# DM3390_Connector_C.net
KiCad netlist of a schematic drawn in Altium Designer
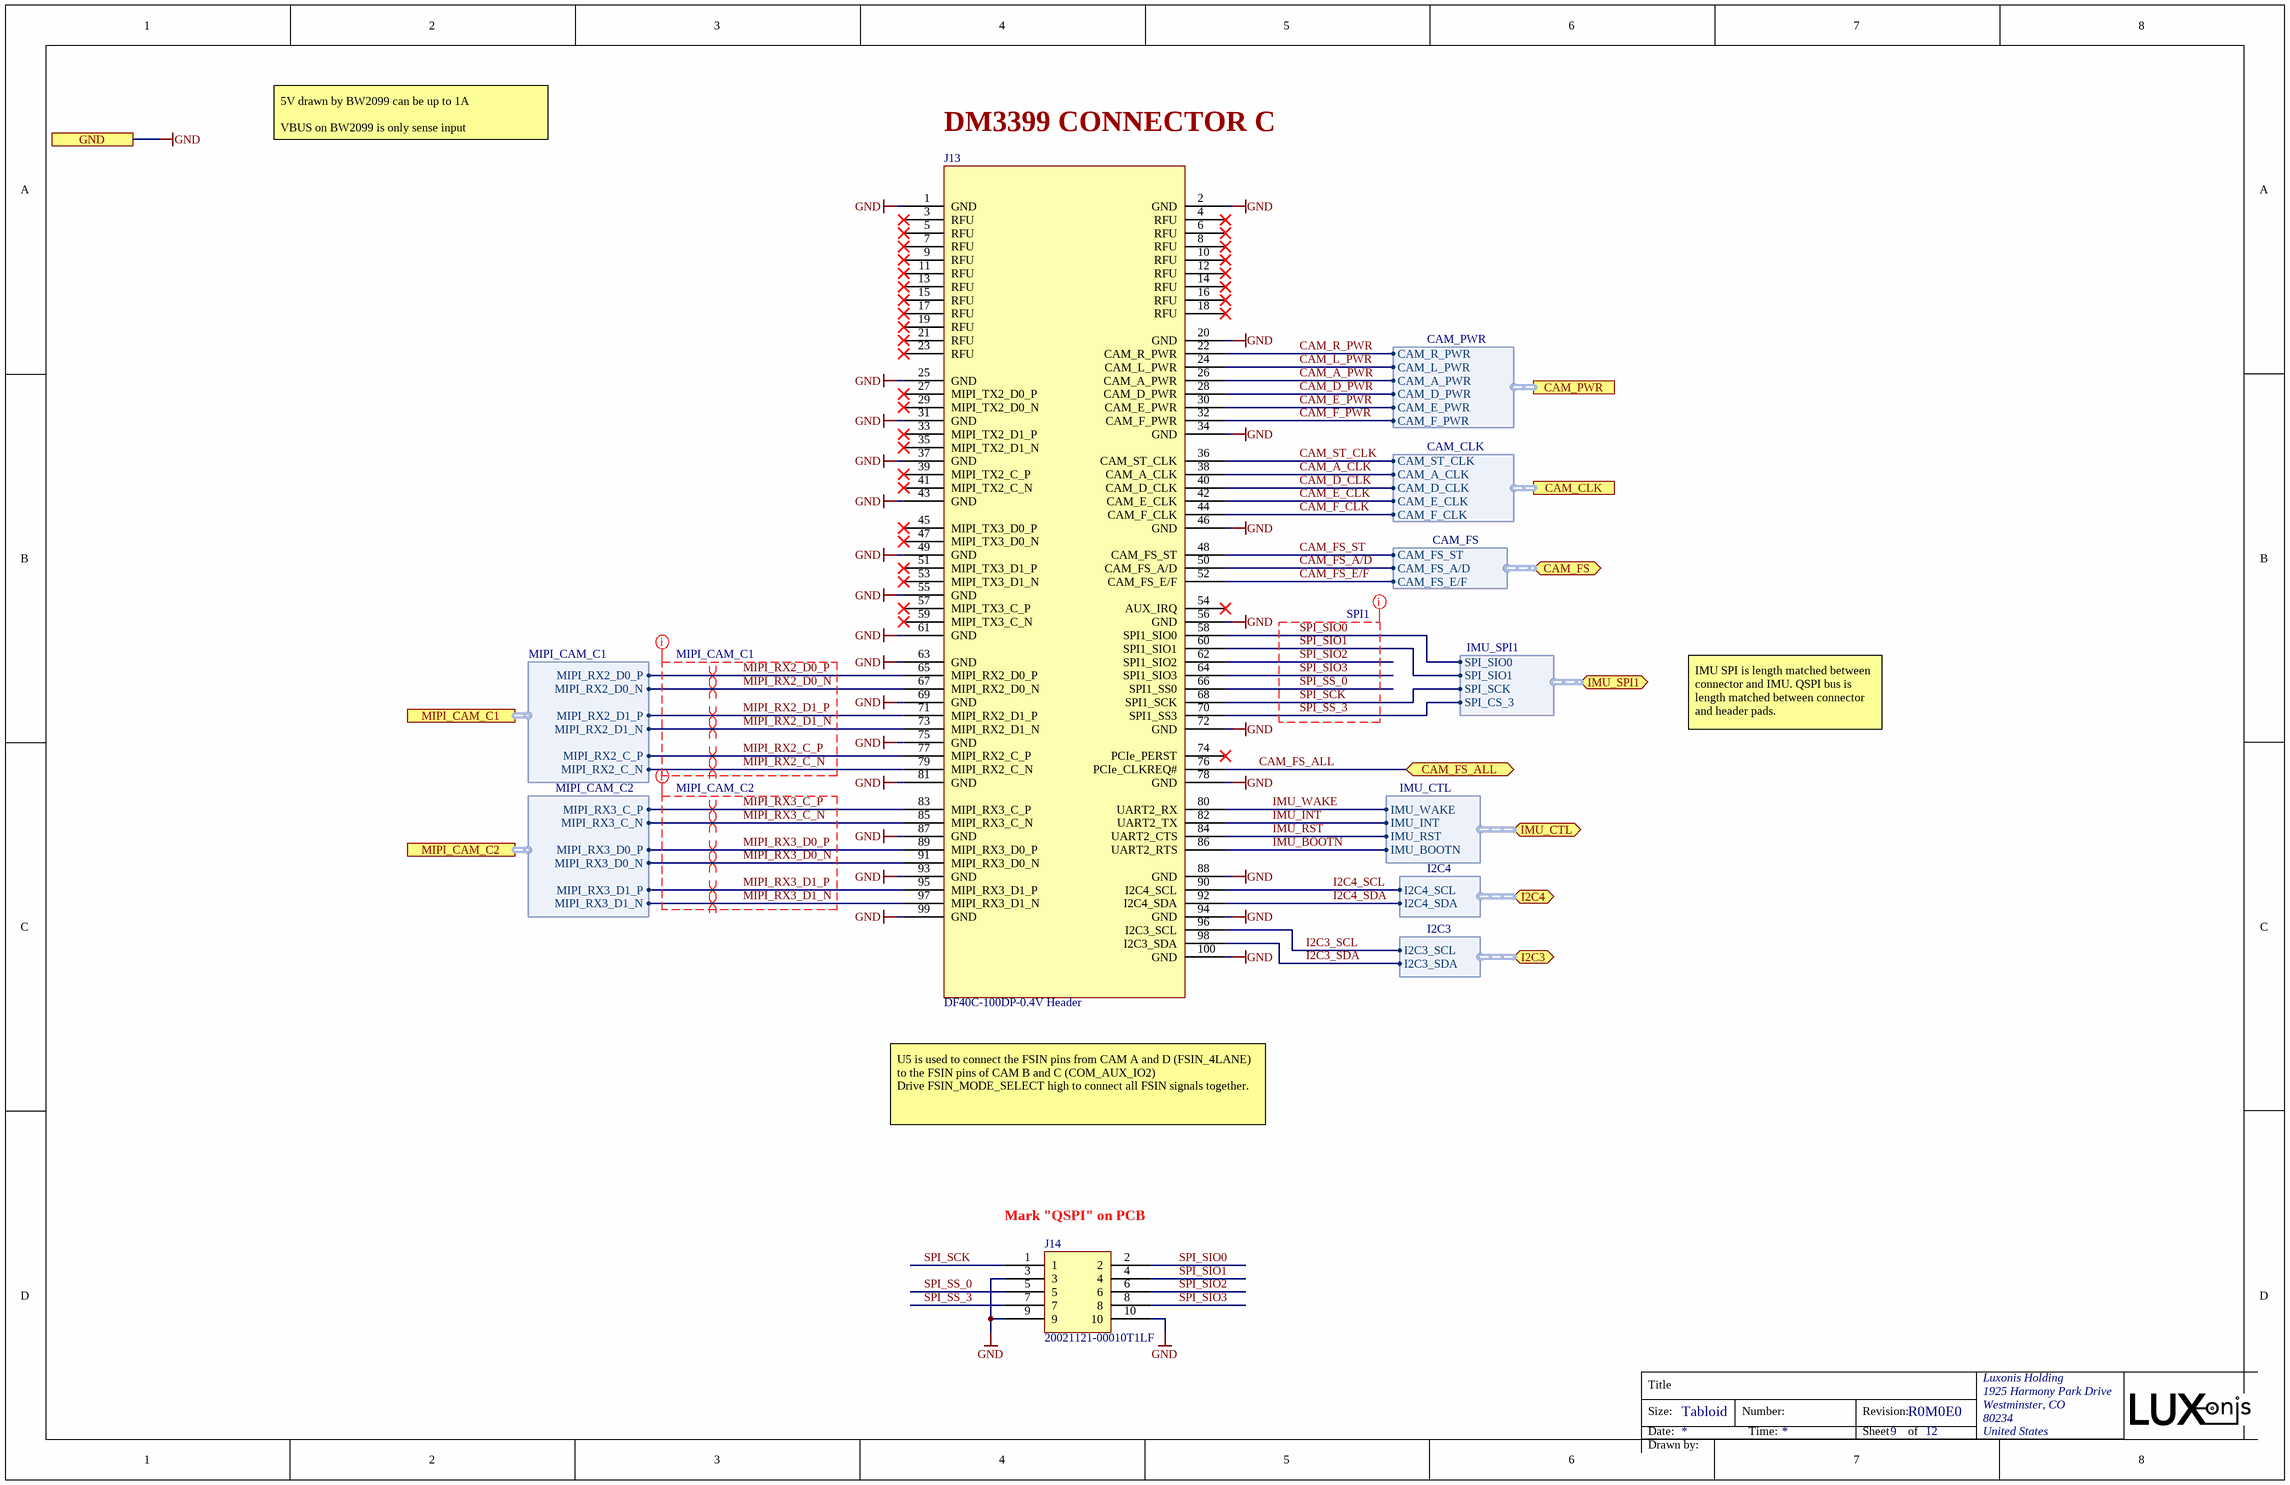
[diagram p0: DM3390_Connector_C.SchDoc]

(export (version "E")
  (design (tool "Eeschema 10.0.6"))
  (components
    (comp (ref "J13")
      (value "DF40C-100DP-0.4V Header")
      (footprint "LuxonisMaster:CON_C_SoM-MAX_DF40HC-3.0-100DS-0.4V_minpad")
      (description "CONN HDR 100POS 0.4MM SMD GOLD BW2099 SYMBOL")
      (fields (field (name "MFG") "Hirose"))
      (libsource (lib "LuxonisMaster") (part "DF40HC(3.0)-100DS-0.4V_OAK-SoM-MAX_C"))
    )
    (comp (ref "J14")
      (value "20021121-00010T1LF")
      (footprint "LuxonisMaster:20021121-00010T1LF")
      (description "CONN HEADER SMD 10POS 1.27MM")
      (libsource (lib "LuxonisMaster") (part "20021121-00010T1LF"))
    )
  )
  (nets
    (net (code "10") (name "/CAM_A_CLK") (class "Default")
      (node (ref "J13") (pin "38") (pinfunction "CAM_A_CLK_38") (pintype "passive"))
    )
    (net (code "11") (name "/CAM_A_PWR") (class "Default")
      (node (ref "J13") (pin "26") (pinfunction "CAM_A_PWR_26") (pintype "passive"))
    )
    (net (code "12") (name "/CAM_D_CLK") (class "Default")
      (node (ref "J13") (pin "40") (pinfunction "CAM_D_CLK_40") (pintype "passive"))
    )
    (net (code "13") (name "/CAM_D_PWR") (class "Default")
      (node (ref "J13") (pin "28") (pinfunction "CAM_D_PWR_28") (pintype "passive"))
    )
    (net (code "14") (name "/CAM_E_CLK") (class "Default")
      (node (ref "J13") (pin "42") (pinfunction "CAM_E_CLK_42") (pintype "passive"))
    )
    (net (code "15") (name "/CAM_E_PWR") (class "Default")
      (node (ref "J13") (pin "30") (pinfunction "CAM_E_PWR_30") (pintype "passive"))
    )
    (net (code "16") (name "/CAM_FS_ALL") (class "Default")
      (node (ref "J13") (pin "76") (pinfunction "PCIe_CLKREQ#_76") (pintype "passive"))
    )
    (net (code "17") (name "/CAM_FS_A{slash}D") (class "Default")
      (node (ref "J13") (pin "50") (pinfunction "CAM_FS_A/D_50") (pintype "passive"))
    )
    (net (code "18") (name "/CAM_FS_E{slash}F") (class "Default")
      (node (ref "J13") (pin "52") (pinfunction "CAM_FS_E/F_52") (pintype "passive"))
    )
    (net (code "19") (name "/CAM_FS_ST") (class "Default")
      (node (ref "J13") (pin "48") (pinfunction "CAM_FS_ST_48") (pintype "passive"))
    )
    (net (code "20") (name "/CAM_F_CLK") (class "Default")
      (node (ref "J13") (pin "44") (pinfunction "CAM_F_CLK_44") (pintype "passive"))
    )
    (net (code "21") (name "/CAM_F_PWR") (class "Default")
      (node (ref "J13") (pin "32") (pinfunction "CAM_F_PWR_32") (pintype "passive"))
    )
    (net (code "22") (name "/CAM_L_PWR") (class "Default")
      (node (ref "J13") (pin "24") (pinfunction "CAM_L_PWR_24") (pintype "passive"))
    )
    (net (code "23") (name "/CAM_R_PWR") (class "Default")
      (node (ref "J13") (pin "22") (pinfunction "CAM_R_PWR_22") (pintype "passive"))
    )
    (net (code "24") (name "/CAM_ST_CLK") (class "Default")
      (node (ref "J13") (pin "36") (pinfunction "CAM_ST_CLK_36") (pintype "passive"))
    )
    (net (code "25") (name "/I2C3_SCL") (class "Default")
      (node (ref "J13") (pin "96") (pinfunction "I2C3_SCL_96") (pintype "passive"))
    )
    (net (code "26") (name "/I2C3_SDA") (class "Default")
      (node (ref "J13") (pin "98") (pinfunction "I2C3_SDA_98") (pintype "passive"))
    )
    (net (code "27") (name "/I2C4_SCL") (class "Default")
      (node (ref "J13") (pin "90") (pinfunction "I2C4_SCL_90") (pintype "passive"))
    )
    (net (code "28") (name "/I2C4_SDA") (class "Default")
      (node (ref "J13") (pin "92") (pinfunction "I2C4_SDA_92") (pintype "passive"))
    )
    (net (code "29") (name "/IMU_BOOTN") (class "Default")
      (node (ref "J13") (pin "86") (pinfunction "UART2_RTS_86") (pintype "passive"))
    )
    (net (code "30") (name "/IMU_INT") (class "Default")
      (node (ref "J13") (pin "82") (pinfunction "UART2_TX_82") (pintype "passive"))
    )
    (net (code "31") (name "/IMU_RST") (class "Default")
      (node (ref "J13") (pin "84") (pinfunction "UART2_CTS_84") (pintype "passive"))
    )
    (net (code "32") (name "/IMU_WAKE") (class "Default")
      (node (ref "J13") (pin "80") (pinfunction "UART2_RX_80") (pintype "passive"))
    )
    (net (code "33") (name "/MIPI_RX2_C_N") (class "Default")
      (node (ref "J13") (pin "79") (pinfunction "MIPI_RX2_C_N_79") (pintype "passive"))
    )
    (net (code "34") (name "/MIPI_RX2_C_P") (class "Default")
      (node (ref "J13") (pin "77") (pinfunction "MIPI_RX2_C_P_77") (pintype "passive"))
    )
    (net (code "35") (name "/MIPI_RX2_D0_N") (class "Default")
      (node (ref "J13") (pin "67") (pinfunction "MIPI_RX2_D0_N_67") (pintype "passive"))
    )
    (net (code "36") (name "/MIPI_RX2_D0_P") (class "Default")
      (node (ref "J13") (pin "65") (pinfunction "MIPI_RX2_D0_P_65") (pintype "passive"))
    )
    (net (code "37") (name "/MIPI_RX2_D1_N") (class "Default")
      (node (ref "J13") (pin "73") (pinfunction "MIPI_RX2_D1_N_73") (pintype "passive"))
    )
    (net (code "38") (name "/MIPI_RX2_D1_P") (class "Default")
      (node (ref "J13") (pin "71") (pinfunction "MIPI_RX2_D1_P_71") (pintype "passive"))
    )
    (net (code "39") (name "/MIPI_RX3_C_N") (class "Default")
      (node (ref "J13") (pin "85") (pinfunction "MIPI_RX3_C_N_85") (pintype "passive"))
    )
    (net (code "40") (name "/MIPI_RX3_C_P") (class "Default")
      (node (ref "J13") (pin "83") (pinfunction "MIPI_RX3_C_P_83") (pintype "passive"))
    )
    (net (code "41") (name "/MIPI_RX3_D0_N") (class "Default")
      (node (ref "J13") (pin "91") (pinfunction "MIPI_RX3_D0_N_91") (pintype "passive"))
    )
    (net (code "42") (name "/MIPI_RX3_D0_P") (class "Default")
      (node (ref "J13") (pin "89") (pinfunction "MIPI_RX3_D0_P_89") (pintype "passive"))
    )
    (net (code "43") (name "/MIPI_RX3_D1_N") (class "Default")
      (node (ref "J13") (pin "97") (pinfunction "MIPI_RX3_D1_N_97") (pintype "passive"))
    )
    (net (code "44") (name "/MIPI_RX3_D1_P") (class "Default")
      (node (ref "J13") (pin "95") (pinfunction "MIPI_RX3_D1_P_95") (pintype "passive"))
    )
    (net (code "45") (name "/SPI_SCK") (class "Default")
      (node (ref "J13") (pin "68") (pinfunction "SPI1_SCK_68") (pintype "passive"))
      (node (ref "J14") (pin "1") (pinfunction "1_1") (pintype "passive"))
    )
    (net (code "46") (name "/SPI_SIO0") (class "Default")
      (node (ref "J13") (pin "58") (pinfunction "SPI1_SIO0_58") (pintype "passive"))
      (node (ref "J14") (pin "2") (pinfunction "2_2") (pintype "passive"))
    )
    (net (code "47") (name "/SPI_SIO1") (class "Default")
      (node (ref "J13") (pin "60") (pinfunction "SPI1_SIO1_60") (pintype "passive"))
      (node (ref "J14") (pin "4") (pinfunction "4_4") (pintype "passive"))
    )
    (net (code "48") (name "/SPI_SIO2") (class "Default")
      (node (ref "J13") (pin "62") (pinfunction "SPI1_SIO2_62") (pintype "passive"))
      (node (ref "J14") (pin "6") (pinfunction "6_6") (pintype "passive"))
    )
    (net (code "49") (name "/SPI_SIO3") (class "Default")
      (node (ref "J13") (pin "64") (pinfunction "SPI1_SIO3_64") (pintype "passive"))
      (node (ref "J14") (pin "8") (pinfunction "8_8") (pintype "passive"))
    )
    (net (code "50") (name "/SPI_SS_0") (class "Default")
      (node (ref "J13") (pin "66") (pinfunction "SPI1_SS0_66") (pintype "passive"))
      (node (ref "J14") (pin "5") (pinfunction "5_5") (pintype "passive"))
    )
    (net (code "51") (name "/SPI_SS_3") (class "Default")
      (node (ref "J13") (pin "70") (pinfunction "SPI1_SS3_70") (pintype "passive"))
      (node (ref "J14") (pin "7") (pinfunction "7_7") (pintype "passive"))
    )
    (net (code "61") (name "GND") (class "Default")
      (node (ref "J13") (pin "1") (pinfunction "GND_1") (pintype "passive"))
      (node (ref "J13") (pin "100") (pinfunction "GND_100") (pintype "passive"))
      (node (ref "J13") (pin "2") (pinfunction "GND_2") (pintype "passive"))
      (node (ref "J13") (pin "20") (pinfunction "GND_20") (pintype "passive"))
      (node (ref "J13") (pin "25") (pinfunction "GND_25") (pintype "passive"))
      (node (ref "J13") (pin "31") (pinfunction "GND_31") (pintype "passive"))
      (node (ref "J13") (pin "34") (pinfunction "GND_34") (pintype "passive"))
      (node (ref "J13") (pin "37") (pinfunction "GND_37") (pintype "passive"))
      (node (ref "J13") (pin "43") (pinfunction "GND_43") (pintype "passive"))
      (node (ref "J13") (pin "46") (pinfunction "GND_46") (pintype "passive"))
      (node (ref "J13") (pin "49") (pinfunction "GND_49") (pintype "passive"))
      (node (ref "J13") (pin "55") (pinfunction "GND_55") (pintype "passive"))
      (node (ref "J13") (pin "56") (pinfunction "GND_56") (pintype "passive"))
      (node (ref "J13") (pin "61") (pinfunction "GND_61") (pintype "passive"))
      (node (ref "J13") (pin "63") (pinfunction "GND_63") (pintype "passive"))
      (node (ref "J13") (pin "69") (pinfunction "GND_69") (pintype "passive"))
      (node (ref "J13") (pin "72") (pinfunction "GND_72") (pintype "passive"))
      (node (ref "J13") (pin "75") (pinfunction "GND_75") (pintype "passive"))
      (node (ref "J13") (pin "78") (pinfunction "GND_78") (pintype "passive"))
      (node (ref "J13") (pin "81") (pinfunction "GND_81") (pintype "passive"))
      (node (ref "J13") (pin "87") (pinfunction "GND_87") (pintype "passive"))
      (node (ref "J13") (pin "88") (pinfunction "GND_88") (pintype "passive"))
      (node (ref "J13") (pin "93") (pinfunction "GND_93") (pintype "passive"))
      (node (ref "J13") (pin "94") (pinfunction "GND_94") (pintype "passive"))
      (node (ref "J13") (pin "99") (pinfunction "GND_99") (pintype "passive"))
      (node (ref "J14") (pin "10") (pinfunction "10_10") (pintype "passive"))
      (node (ref "J14") (pin "3") (pinfunction "3_3") (pintype "passive"))
      (node (ref "J14") (pin "9") (pinfunction "9_9") (pintype "passive"))
    )
    (net (code "62") (name "unconnected-(J13-AUX_IRQ-Pad54)") (class "Default")
      (node (ref "J13") (pin "54") (pinfunction "AUX_IRQ_54") (pintype "passive+no_connect"))
    )
    (net (code "63") (name "unconnected-(J13-MIPI_TX2_C_N-Pad41)") (class "Default")
      (node (ref "J13") (pin "41") (pinfunction "MIPI_TX2_C_N_41") (pintype "passive+no_connect"))
    )
    (net (code "64") (name "unconnected-(J13-MIPI_TX2_C_P-Pad39)") (class "Default")
      (node (ref "J13") (pin "39") (pinfunction "MIPI_TX2_C_P_39") (pintype "passive+no_connect"))
    )
    (net (code "65") (name "unconnected-(J13-MIPI_TX2_D0_N-Pad29)") (class "Default")
      (node (ref "J13") (pin "29") (pinfunction "MIPI_TX2_D0_N_29") (pintype "passive+no_connect"))
    )
    (net (code "66") (name "unconnected-(J13-MIPI_TX2_D0_P-Pad27)") (class "Default")
      (node (ref "J13") (pin "27") (pinfunction "MIPI_TX2_D0_P_27") (pintype "passive+no_connect"))
    )
    (net (code "67") (name "unconnected-(J13-MIPI_TX2_D1_N-Pad35)") (class "Default")
      (node (ref "J13") (pin "35") (pinfunction "MIPI_TX2_D1_N_35") (pintype "passive+no_connect"))
    )
    (net (code "68") (name "unconnected-(J13-MIPI_TX2_D1_P-Pad33)") (class "Default")
      (node (ref "J13") (pin "33") (pinfunction "MIPI_TX2_D1_P_33") (pintype "passive+no_connect"))
    )
    (net (code "69") (name "unconnected-(J13-MIPI_TX3_C_N-Pad59)") (class "Default")
      (node (ref "J13") (pin "59") (pinfunction "MIPI_TX3_C_N_59") (pintype "passive+no_connect"))
    )
    (net (code "70") (name "unconnected-(J13-MIPI_TX3_C_P-Pad57)") (class "Default")
      (node (ref "J13") (pin "57") (pinfunction "MIPI_TX3_C_P_57") (pintype "passive+no_connect"))
    )
    (net (code "71") (name "unconnected-(J13-MIPI_TX3_D0_N-Pad47)") (class "Default")
      (node (ref "J13") (pin "47") (pinfunction "MIPI_TX3_D0_N_47") (pintype "passive+no_connect"))
    )
    (net (code "72") (name "unconnected-(J13-MIPI_TX3_D0_P-Pad45)") (class "Default")
      (node (ref "J13") (pin "45") (pinfunction "MIPI_TX3_D0_P_45") (pintype "passive+no_connect"))
    )
    (net (code "73") (name "unconnected-(J13-MIPI_TX3_D1_N-Pad53)") (class "Default")
      (node (ref "J13") (pin "53") (pinfunction "MIPI_TX3_D1_N_53") (pintype "passive+no_connect"))
    )
    (net (code "74") (name "unconnected-(J13-MIPI_TX3_D1_P-Pad51)") (class "Default")
      (node (ref "J13") (pin "51") (pinfunction "MIPI_TX3_D1_P_51") (pintype "passive+no_connect"))
    )
    (net (code "75") (name "unconnected-(J13-PCIe_PERST-Pad74)") (class "Default")
      (node (ref "J13") (pin "74") (pinfunction "PCIe_PERST_74") (pintype "passive+no_connect"))
    )
    (net (code "76") (name "unconnected-(J13-RFU-Pad3)") (class "Default")
      (node (ref "J13") (pin "3") (pinfunction "RFU_3") (pintype "passive+no_connect"))
    )
    (net (code "77") (name "unconnected-(J13-RFU-Pad4)") (class "Default")
      (node (ref "J13") (pin "4") (pinfunction "RFU_4") (pintype "passive+no_connect"))
    )
    (net (code "78") (name "unconnected-(J13-RFU-Pad5)") (class "Default")
      (node (ref "J13") (pin "5") (pinfunction "RFU_5") (pintype "passive+no_connect"))
    )
    (net (code "79") (name "unconnected-(J13-RFU-Pad6)") (class "Default")
      (node (ref "J13") (pin "6") (pinfunction "RFU_6") (pintype "passive+no_connect"))
    )
    (net (code "80") (name "unconnected-(J13-RFU-Pad7)") (class "Default")
      (node (ref "J13") (pin "7") (pinfunction "RFU_7") (pintype "passive+no_connect"))
    )
    (net (code "81") (name "unconnected-(J13-RFU-Pad8)") (class "Default")
      (node (ref "J13") (pin "8") (pinfunction "RFU_8") (pintype "passive+no_connect"))
    )
    (net (code "82") (name "unconnected-(J13-RFU-Pad9)") (class "Default")
      (node (ref "J13") (pin "9") (pinfunction "RFU_9") (pintype "passive+no_connect"))
    )
    (net (code "83") (name "unconnected-(J13-RFU-Pad10)") (class "Default")
      (node (ref "J13") (pin "10") (pinfunction "RFU_10") (pintype "passive+no_connect"))
    )
    (net (code "84") (name "unconnected-(J13-RFU-Pad11)") (class "Default")
      (node (ref "J13") (pin "11") (pinfunction "RFU_11") (pintype "passive+no_connect"))
    )
    (net (code "85") (name "unconnected-(J13-RFU-Pad12)") (class "Default")
      (node (ref "J13") (pin "12") (pinfunction "RFU_12") (pintype "passive+no_connect"))
    )
    (net (code "86") (name "unconnected-(J13-RFU-Pad13)") (class "Default")
      (node (ref "J13") (pin "13") (pinfunction "RFU_13") (pintype "passive+no_connect"))
    )
    (net (code "87") (name "unconnected-(J13-RFU-Pad14)") (class "Default")
      (node (ref "J13") (pin "14") (pinfunction "RFU_14") (pintype "passive+no_connect"))
    )
    (net (code "88") (name "unconnected-(J13-RFU-Pad15)") (class "Default")
      (node (ref "J13") (pin "15") (pinfunction "RFU_15") (pintype "passive+no_connect"))
    )
    (net (code "89") (name "unconnected-(J13-RFU-Pad16)") (class "Default")
      (node (ref "J13") (pin "16") (pinfunction "RFU_16") (pintype "passive+no_connect"))
    )
    (net (code "90") (name "unconnected-(J13-RFU-Pad17)") (class "Default")
      (node (ref "J13") (pin "17") (pinfunction "RFU_17") (pintype "passive+no_connect"))
    )
    (net (code "91") (name "unconnected-(J13-RFU-Pad18)") (class "Default")
      (node (ref "J13") (pin "18") (pinfunction "RFU_18") (pintype "passive+no_connect"))
    )
    (net (code "92") (name "unconnected-(J13-RFU-Pad19)") (class "Default")
      (node (ref "J13") (pin "19") (pinfunction "RFU_19") (pintype "passive+no_connect"))
    )
    (net (code "93") (name "unconnected-(J13-RFU-Pad21)") (class "Default")
      (node (ref "J13") (pin "21") (pinfunction "RFU_21") (pintype "passive+no_connect"))
    )
    (net (code "94") (name "unconnected-(J13-RFU-Pad23)") (class "Default")
      (node (ref "J13") (pin "23") (pinfunction "RFU_23") (pintype "passive+no_connect"))
    )
  )
)
